# PicoModuleInterface.net
KiCad netlist of a schematic drawn in Altium Designer
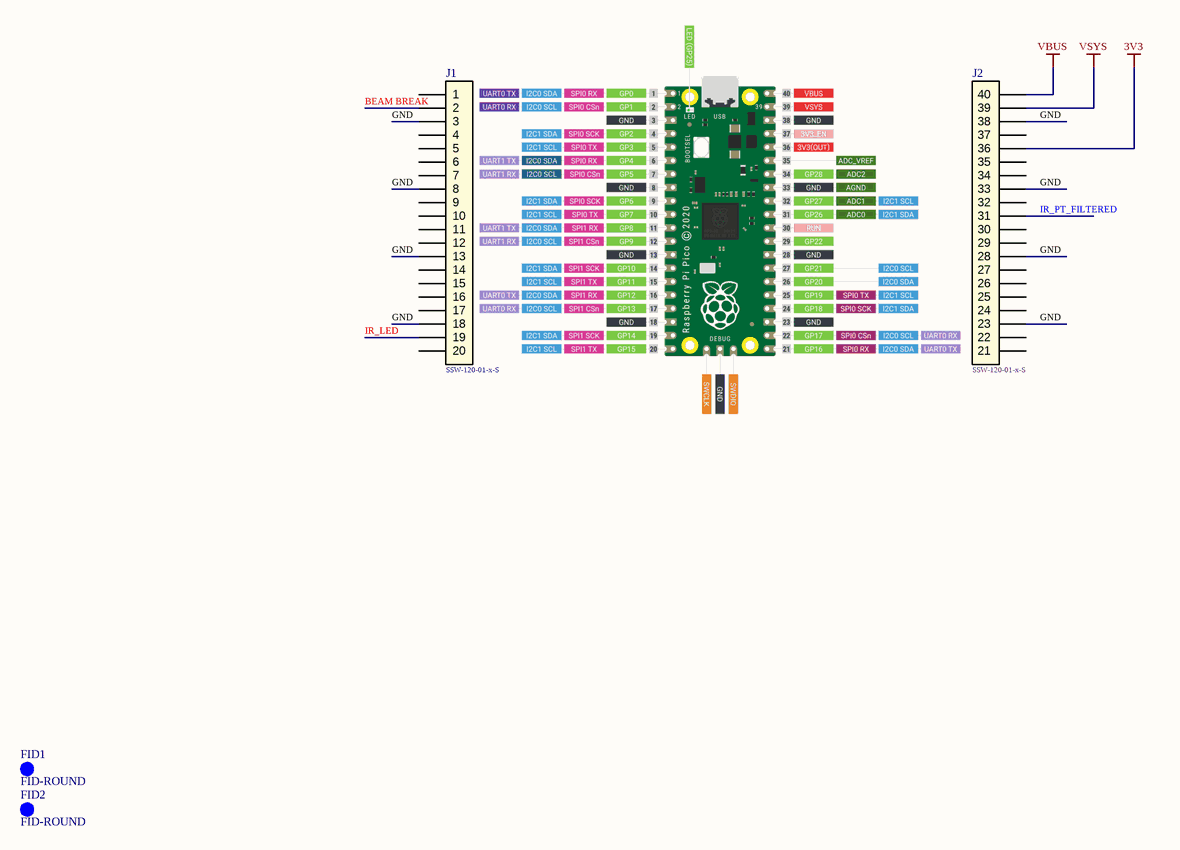
[diagram p0: PicoModuleInterface.SchDoc]

(export (version "E")
  (design (tool "Eeschema 10.0.6"))
  (components
    (comp (ref "FID1")
      (value "FID-ROUND")
      (footprint "Fid_Round")
      (description "Round Fiducial")
      (libsource (lib "Sainsbury Wellcome Centre") (part "Fid_Round"))
    )
    (comp (ref "FID2")
      (value "FID-ROUND")
      (footprint "Fid_Round")
      (description "Round Fiducial")
      (libsource (lib "Sainsbury Wellcome Centre") (part "Fid_Round"))
    )
    (comp (ref "J1")
      (value "SSW-120-01-x-S")
      (footprint "SAMTEC_SSW-120-01-G-S")
      (description "Conn Socket Strip SKT 20 POS 2.54mm Solder ST Thru-Hole")
      (libsource (lib "Sainsbury Wellcome Centre") (part "Jack 20x1"))
    )
    (comp (ref "J2")
      (value "SSW-120-01-x-S - 21-40")
      (footprint "SAMTEC_SSW-120-01-G-S - 21-40")
      (description "Conn Socket Strip SKT 20 POS 2.54mm Solder ST Thru-Hole (pins 21 - 40)")
      (libsource (lib "Sainsbury Wellcome Centre") (part "Jack 20x1 21-40"))
    )
  )
  (nets
    (net (code "1") (name "/BEAM BREAK") (class "Default")
      (node (ref "J1") (pin "2") (pinfunction "2_2") (pintype "passive"))
    )
    (net (code "2") (name "/GND") (class "Default")
      (node (ref "J1") (pin "13") (pinfunction "13_13") (pintype "passive"))
      (node (ref "J1") (pin "18") (pinfunction "18_18") (pintype "passive"))
      (node (ref "J1") (pin "3") (pinfunction "3_3") (pintype "passive"))
      (node (ref "J1") (pin "8") (pinfunction "8_8") (pintype "passive"))
      (node (ref "J2") (pin "23") (pinfunction "23_23") (pintype "passive"))
      (node (ref "J2") (pin "28") (pinfunction "28_28") (pintype "passive"))
      (node (ref "J2") (pin "33") (pinfunction "33_33") (pintype "passive"))
      (node (ref "J2") (pin "38") (pinfunction "38_38") (pintype "passive"))
    )
    (net (code "3") (name "/IR_LED") (class "Default")
      (node (ref "J1") (pin "19") (pinfunction "19_19") (pintype "passive"))
    )
    (net (code "4") (name "/IR_PT_FILTERED") (class "Default")
      (node (ref "J2") (pin "31") (pinfunction "31_31") (pintype "passive"))
    )
    (net (code "5") (name "3V3") (class "Default")
      (node (ref "J2") (pin "36") (pinfunction "36_36") (pintype "passive"))
    )
    (net (code "6") (name "VBUS") (class "Default")
      (node (ref "J2") (pin "40") (pinfunction "40_40") (pintype "passive"))
    )
    (net (code "7") (name "VSYS") (class "Default")
      (node (ref "J2") (pin "39") (pinfunction "39_39") (pintype "passive"))
    )
    (net (code "8") (name "unconnected-(J1-Pad1)") (class "Default")
      (node (ref "J1") (pin "1") (pinfunction "1_1") (pintype "passive"))
    )
    (net (code "9") (name "unconnected-(J1-Pad4)") (class "Default")
      (node (ref "J1") (pin "4") (pinfunction "4_4") (pintype "passive"))
    )
    (net (code "10") (name "unconnected-(J1-Pad5)") (class "Default")
      (node (ref "J1") (pin "5") (pinfunction "5_5") (pintype "passive"))
    )
    (net (code "11") (name "unconnected-(J1-Pad6)") (class "Default")
      (node (ref "J1") (pin "6") (pinfunction "6_6") (pintype "passive"))
    )
    (net (code "12") (name "unconnected-(J1-Pad7)") (class "Default")
      (node (ref "J1") (pin "7") (pinfunction "7_7") (pintype "passive"))
    )
    (net (code "13") (name "unconnected-(J1-Pad9)") (class "Default")
      (node (ref "J1") (pin "9") (pinfunction "9_9") (pintype "passive"))
    )
    (net (code "14") (name "unconnected-(J1-Pad10)") (class "Default")
      (node (ref "J1") (pin "10") (pinfunction "10_10") (pintype "passive"))
    )
    (net (code "15") (name "unconnected-(J1-Pad11)") (class "Default")
      (node (ref "J1") (pin "11") (pinfunction "11_11") (pintype "passive"))
    )
    (net (code "16") (name "unconnected-(J1-Pad12)") (class "Default")
      (node (ref "J1") (pin "12") (pinfunction "12_12") (pintype "passive"))
    )
    (net (code "17") (name "unconnected-(J1-Pad14)") (class "Default")
      (node (ref "J1") (pin "14") (pinfunction "14_14") (pintype "passive"))
    )
    (net (code "18") (name "unconnected-(J1-Pad15)") (class "Default")
      (node (ref "J1") (pin "15") (pinfunction "15_15") (pintype "passive"))
    )
    (net (code "19") (name "unconnected-(J1-Pad16)") (class "Default")
      (node (ref "J1") (pin "16") (pinfunction "16_16") (pintype "passive"))
    )
    (net (code "20") (name "unconnected-(J1-Pad17)") (class "Default")
      (node (ref "J1") (pin "17") (pinfunction "17_17") (pintype "passive"))
    )
    (net (code "21") (name "unconnected-(J1-Pad20)") (class "Default")
      (node (ref "J1") (pin "20") (pinfunction "20_20") (pintype "passive"))
    )
    (net (code "22") (name "unconnected-(J2-Pad21)") (class "Default")
      (node (ref "J2") (pin "21") (pinfunction "21_21") (pintype "passive"))
    )
    (net (code "23") (name "unconnected-(J2-Pad22)") (class "Default")
      (node (ref "J2") (pin "22") (pinfunction "22_22") (pintype "passive"))
    )
    (net (code "24") (name "unconnected-(J2-Pad24)") (class "Default")
      (node (ref "J2") (pin "24") (pinfunction "24_24") (pintype "passive"))
    )
    (net (code "25") (name "unconnected-(J2-Pad25)") (class "Default")
      (node (ref "J2") (pin "25") (pinfunction "25_25") (pintype "passive"))
    )
    (net (code "26") (name "unconnected-(J2-Pad26)") (class "Default")
      (node (ref "J2") (pin "26") (pinfunction "26_26") (pintype "passive"))
    )
    (net (code "27") (name "unconnected-(J2-Pad27)") (class "Default")
      (node (ref "J2") (pin "27") (pinfunction "27_27") (pintype "passive"))
    )
    (net (code "28") (name "unconnected-(J2-Pad29)") (class "Default")
      (node (ref "J2") (pin "29") (pinfunction "29_29") (pintype "passive"))
    )
    (net (code "29") (name "unconnected-(J2-Pad30)") (class "Default")
      (node (ref "J2") (pin "30") (pinfunction "30_30") (pintype "passive"))
    )
    (net (code "30") (name "unconnected-(J2-Pad32)") (class "Default")
      (node (ref "J2") (pin "32") (pinfunction "32_32") (pintype "passive"))
    )
    (net (code "31") (name "unconnected-(J2-Pad34)") (class "Default")
      (node (ref "J2") (pin "34") (pinfunction "34_34") (pintype "passive"))
    )
    (net (code "32") (name "unconnected-(J2-Pad35)") (class "Default")
      (node (ref "J2") (pin "35") (pinfunction "35_35") (pintype "passive"))
    )
    (net (code "33") (name "unconnected-(J2-Pad37)") (class "Default")
      (node (ref "J2") (pin "37") (pinfunction "37_37") (pintype "passive"))
    )
  )
)
